# Ctrol1.net
KiCad netlist of a schematic drawn in Altium Designer
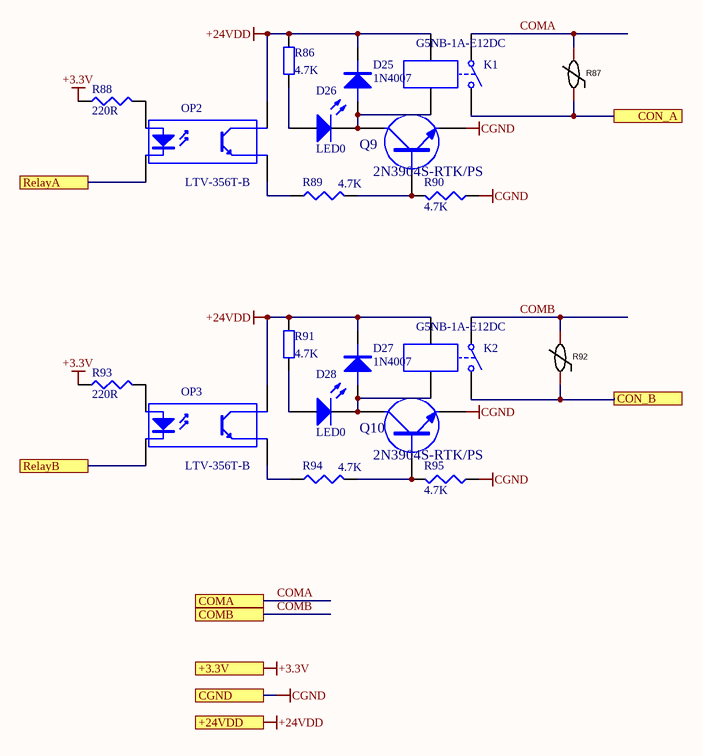
[diagram p0: Ctrol1.SchDoc]

(export (version "E")
  (design (tool "Eeschema 10.0.6"))
  (components
    (comp (ref "D25") (value "1N4007") (footprint "DO-213AB") (libsource (lib "*") (part "DIODE")))
    (comp (ref "D26")
      (value "LED0")
      (footprint "0805LED")
      (description "品牌： 国星光电 型号： NCD0805B2 发光颜色：蓝灯 贴片LED；0805蓝色；2012蓝色；透镜颜色：无色透明；发光角度：130°；功率：72mW；工作温度：-30℃~+85℃；")
      (fields (field (name "PUBLISHER") "Altium Limited"))
      (libsource (lib "Miscellaneous Devices") (part "LED0"))
    )
    (comp (ref "D27") (value "1N4007") (footprint "DO-213AB") (libsource (lib "*") (part "DIODE")))
    (comp (ref "D28")
      (value "LED0")
      (footprint "0805LED")
      (description "品牌： 国星光电 型号： NCD0805B2 发光颜色：蓝灯 贴片LED；0805蓝色；2012蓝色；透镜颜色：无色透明；发光角度：130°；功率：72mW；工作温度：-30℃~+85℃；")
      (fields (field (name "PUBLISHER") "Altium Limited"))
      (libsource (lib "Miscellaneous Devices") (part "LED0"))
    )
    (comp (ref "K1")
      (value "G5NB-1A-E12DC")
      (footprint "G5NB-1A-E")
      (description "品牌： OMRON(欧姆龙) 型号： G5NB-1A-E DC12 封装： 插件,7x20.4mm")
      (fields (field (name "PUBLISHER") "Altium Limited"))
      (libsource (lib "main board fo stk") (part "Relay-G5NB-1A-E"))
    )
    (comp (ref "K2")
      (value "G5NB-1A-E12DC")
      (footprint "G5NB-1A-E")
      (description "品牌： OMRON(欧姆龙) 型号： G5NB-1A-E DC12 封装： 插件,7x20.4mm")
      (fields (field (name "PUBLISHER") "Altium Limited"))
      (libsource (lib "main board fo stk") (part "Relay-G5NB-1A-E"))
    )
    (comp (ref "OP2")
      (value "LTV-356T-B")
      (footprint "TLV-356")
      (description "品牌名称\r\nLITEON(光宝)\r\n商品型号\r\n\r\nLTV-356T-B\r\n商品编号\r\n\r\nC10804\r\n商品封装\r\n\r\nSOP-4-2.54mm")
      (libsource (lib "*") (part "OPTOISO1"))
    )
    (comp (ref "OP3")
      (value "LTV-356T-B")
      (footprint "TLV-356")
      (description "品牌名称\r\nLITEON(光宝)\r\n商品型号\r\n\r\nLTV-356T-B\r\n商品编号\r\n\r\nC10804\r\n商品封装\r\n\r\nSOP-4-2.54mm")
      (libsource (lib "*") (part "OPTOISO1"))
    )
    (comp (ref "Q9") (value "2N3904S-RTK/PS") (footprint "SOT-23") (libsource (lib "*") (part "8050")))
    (comp (ref "Q10") (value "2N3904S-RTK/PS") (footprint "SOT-23") (libsource (lib "*") (part "8050")))
    (comp (ref "R86")
      (value "4.7K")
      (footprint "0805R")
      (description "品牌： UNI-ROYAL(厚声) 型号： 0805W8F4701T5E 电阻类型：厚膜电阻 阻值：4.7kΩ 精度：±1% 功率：125mW 温度系数：±100ppm/℃")
      (fields (field (name "PUBLISHER") "Altium Limited"))
      (libsource (lib "Miscellaneous Devices") (part "Res2"))
    )
    (comp (ref "R87")
      (value "RM10D471KD14E100")
      (footprint "YAMINGDIANZU")
      (fields (field (name "MANUFACTURER") "Dersonic(德尔创)"))
      (libsource (lib "altium-import") (part "root_1_RM10D471KD14E100_"))
    )
    (comp (ref "R88")
      (value "220R")
      (footprint "0805R")
      (description "品牌： UNI-ROYAL(厚声) 型号： 0805W8J0221T5E 电阻类型：厚膜电阻 阻值：220Ω 精度：±5% 功率：125mW 温度系数：±100ppm/℃")
      (libsource (lib "*") (part "RES1"))
    )
    (comp (ref "R89")
      (value "4.7K")
      (footprint "0805R")
      (description "品牌： UNI-ROYAL(厚声) 型号： 0805W8F4701T5E 电阻类型：厚膜电阻 阻值：4.7kΩ 精度：±1% 功率：125mW 温度系数：±100ppm/℃")
      (libsource (lib "*") (part "RES1"))
    )
    (comp (ref "R90")
      (value "4.7K")
      (footprint "0805R")
      (description "品牌： UNI-ROYAL(厚声) 型号： 0805W8F4701T5E 电阻类型：厚膜电阻 阻值：4.7kΩ 精度：±1% 功率：125mW 温度系数：±100ppm/℃")
      (libsource (lib "*") (part "RES1"))
    )
    (comp (ref "R91")
      (value "4.7K")
      (footprint "0805R")
      (description "品牌： UNI-ROYAL(厚声) 型号： 0805W8F4701T5E 电阻类型：厚膜电阻 阻值：4.7kΩ 精度：±1% 功率：125mW 温度系数：±100ppm/℃")
      (fields (field (name "PUBLISHER") "Altium Limited"))
      (libsource (lib "Miscellaneous Devices") (part "Res2"))
    )
    (comp (ref "R92")
      (value "RM10D471KD14E100")
      (footprint "YAMINGDIANZU")
      (fields (field (name "MANUFACTURER") "Dersonic(德尔创)"))
      (libsource (lib "altium-import") (part "root_1_RM10D471KD14E100_"))
    )
    (comp (ref "R93")
      (value "220R")
      (footprint "0805R")
      (description "品牌： UNI-ROYAL(厚声) 型号： 0805W8J0221T5E 电阻类型：厚膜电阻 阻值：220Ω 精度：±5% 功率：125mW 温度系数：±100ppm/℃")
      (libsource (lib "*") (part "RES1"))
    )
    (comp (ref "R94")
      (value "4.7K")
      (footprint "0805R")
      (description "品牌： UNI-ROYAL(厚声) 型号： 0805W8F4701T5E 电阻类型：厚膜电阻 阻值：4.7kΩ 精度：±1% 功率：125mW 温度系数：±100ppm/℃")
      (libsource (lib "*") (part "RES1"))
    )
    (comp (ref "R95")
      (value "4.7K")
      (footprint "0805R")
      (description "品牌： UNI-ROYAL(厚声) 型号： 0805W8F4701T5E 电阻类型：厚膜电阻 阻值：4.7kΩ 精度：±1% 功率：125mW 温度系数：±100ppm/℃")
      (libsource (lib "*") (part "RES1"))
    )
  )
  (nets
    (net (code "1") (name "+3.3V") (class "Default")
      (node (ref "R88") (pin "1") (pinfunction "1_1") (pintype "passive"))
      (node (ref "R93") (pin "1") (pinfunction "1_1") (pintype "passive"))
    )
    (net (code "2") (name "+24VDD") (class "Default")
      (node (ref "D25") (pin "2") (pinfunction "K_2") (pintype "passive"))
      (node (ref "D27") (pin "2") (pinfunction "K_2") (pintype "passive"))
      (node (ref "K1") (pin "1") (pinfunction "1_1") (pintype "passive"))
      (node (ref "K2") (pin "1") (pinfunction "1_1") (pintype "passive"))
      (node (ref "OP2") (pin "4") (pinfunction "C_4") (pintype "passive"))
      (node (ref "OP3") (pin "4") (pinfunction "C_4") (pintype "passive"))
      (node (ref "R86") (pin "1") (pinfunction "1_1") (pintype "passive"))
      (node (ref "R91") (pin "1") (pinfunction "1_1") (pintype "passive"))
    )
    (net (code "3") (name "/COMA") (class "Default")
      (node (ref "K1") (pin "2") (pinfunction "2_2") (pintype "passive"))
      (node (ref "R87") (pin "2") (pinfunction "2_2") (pintype "passive"))
    )
    (net (code "4") (name "/COMB") (class "Default")
      (node (ref "K2") (pin "2") (pinfunction "2_2") (pintype "passive"))
      (node (ref "R92") (pin "2") (pinfunction "2_2") (pintype "passive"))
    )
    (net (code "5") (name "/CON_A") (class "Default")
      (node (ref "K1") (pin "3") (pinfunction "3_3") (pintype "passive"))
      (node (ref "R87") (pin "1") (pinfunction "1_1") (pintype "passive"))
    )
    (net (code "6") (name "/CON_B") (class "Default")
      (node (ref "K2") (pin "3") (pinfunction "3_3") (pintype "passive"))
      (node (ref "R92") (pin "1") (pinfunction "1_1") (pintype "passive"))
    )
    (net (code "7") (name "/RelayA") (class "Default")
      (node (ref "OP2") (pin "2") (pinfunction "K_2") (pintype "passive"))
    )
    (net (code "8") (name "/RelayB") (class "Default")
      (node (ref "OP3") (pin "2") (pinfunction "K_2") (pintype "passive"))
    )
    (net (code "9") (name "CGND") (class "Default")
      (node (ref "Q10") (pin "2") (pinfunction "E_2") (pintype "passive"))
      (node (ref "Q9") (pin "2") (pinfunction "E_2") (pintype "passive"))
      (node (ref "R90") (pin "1") (pinfunction "1_1") (pintype "passive"))
      (node (ref "R95") (pin "1") (pinfunction "1_1") (pintype "passive"))
    )
    (net (code "10") (name "Net-(D25-A)") (class "Default")
      (node (ref "D25") (pin "1") (pinfunction "A_1") (pintype "passive"))
      (node (ref "D26") (pin "2") (pinfunction "K_2") (pintype "passive"))
      (node (ref "K1") (pin "4") (pinfunction "4_4") (pintype "passive"))
      (node (ref "Q9") (pin "3") (pinfunction "C_3") (pintype "passive"))
    )
    (net (code "11") (name "Net-(D26-A)") (class "Default")
      (node (ref "D26") (pin "1") (pinfunction "A_1") (pintype "passive"))
      (node (ref "R86") (pin "2") (pinfunction "2_2") (pintype "passive"))
    )
    (net (code "12") (name "Net-(D27-A)") (class "Default")
      (node (ref "D27") (pin "1") (pinfunction "A_1") (pintype "passive"))
      (node (ref "D28") (pin "2") (pinfunction "K_2") (pintype "passive"))
      (node (ref "K2") (pin "4") (pinfunction "4_4") (pintype "passive"))
      (node (ref "Q10") (pin "3") (pinfunction "C_3") (pintype "passive"))
    )
    (net (code "13") (name "Net-(D28-A)") (class "Default")
      (node (ref "D28") (pin "1") (pinfunction "A_1") (pintype "passive"))
      (node (ref "R91") (pin "2") (pinfunction "2_2") (pintype "passive"))
    )
    (net (code "14") (name "Net-(OP2-A)") (class "Default")
      (node (ref "OP2") (pin "1") (pinfunction "A_1") (pintype "passive"))
      (node (ref "R88") (pin "2") (pinfunction "2_2") (pintype "passive"))
    )
    (net (code "15") (name "Net-(OP2-E)") (class "Default")
      (node (ref "OP2") (pin "3") (pinfunction "E_3") (pintype "passive"))
      (node (ref "R89") (pin "1") (pinfunction "1_1") (pintype "passive"))
    )
    (net (code "16") (name "Net-(OP3-A)") (class "Default")
      (node (ref "OP3") (pin "1") (pinfunction "A_1") (pintype "passive"))
      (node (ref "R93") (pin "2") (pinfunction "2_2") (pintype "passive"))
    )
    (net (code "17") (name "Net-(OP3-E)") (class "Default")
      (node (ref "OP3") (pin "3") (pinfunction "E_3") (pintype "passive"))
      (node (ref "R94") (pin "1") (pinfunction "1_1") (pintype "passive"))
    )
    (net (code "18") (name "Net-(Q9-B)") (class "Default")
      (node (ref "Q9") (pin "1") (pinfunction "B_1") (pintype "passive"))
      (node (ref "R89") (pin "2") (pinfunction "2_2") (pintype "passive"))
      (node (ref "R90") (pin "2") (pinfunction "2_2") (pintype "passive"))
    )
    (net (code "19") (name "Net-(Q10-B)") (class "Default")
      (node (ref "Q10") (pin "1") (pinfunction "B_1") (pintype "passive"))
      (node (ref "R94") (pin "2") (pinfunction "2_2") (pintype "passive"))
      (node (ref "R95") (pin "2") (pinfunction "2_2") (pintype "passive"))
    )
  )
)
